# timerV2.net
KiCad netlist of a schematic drawn in EAGLE
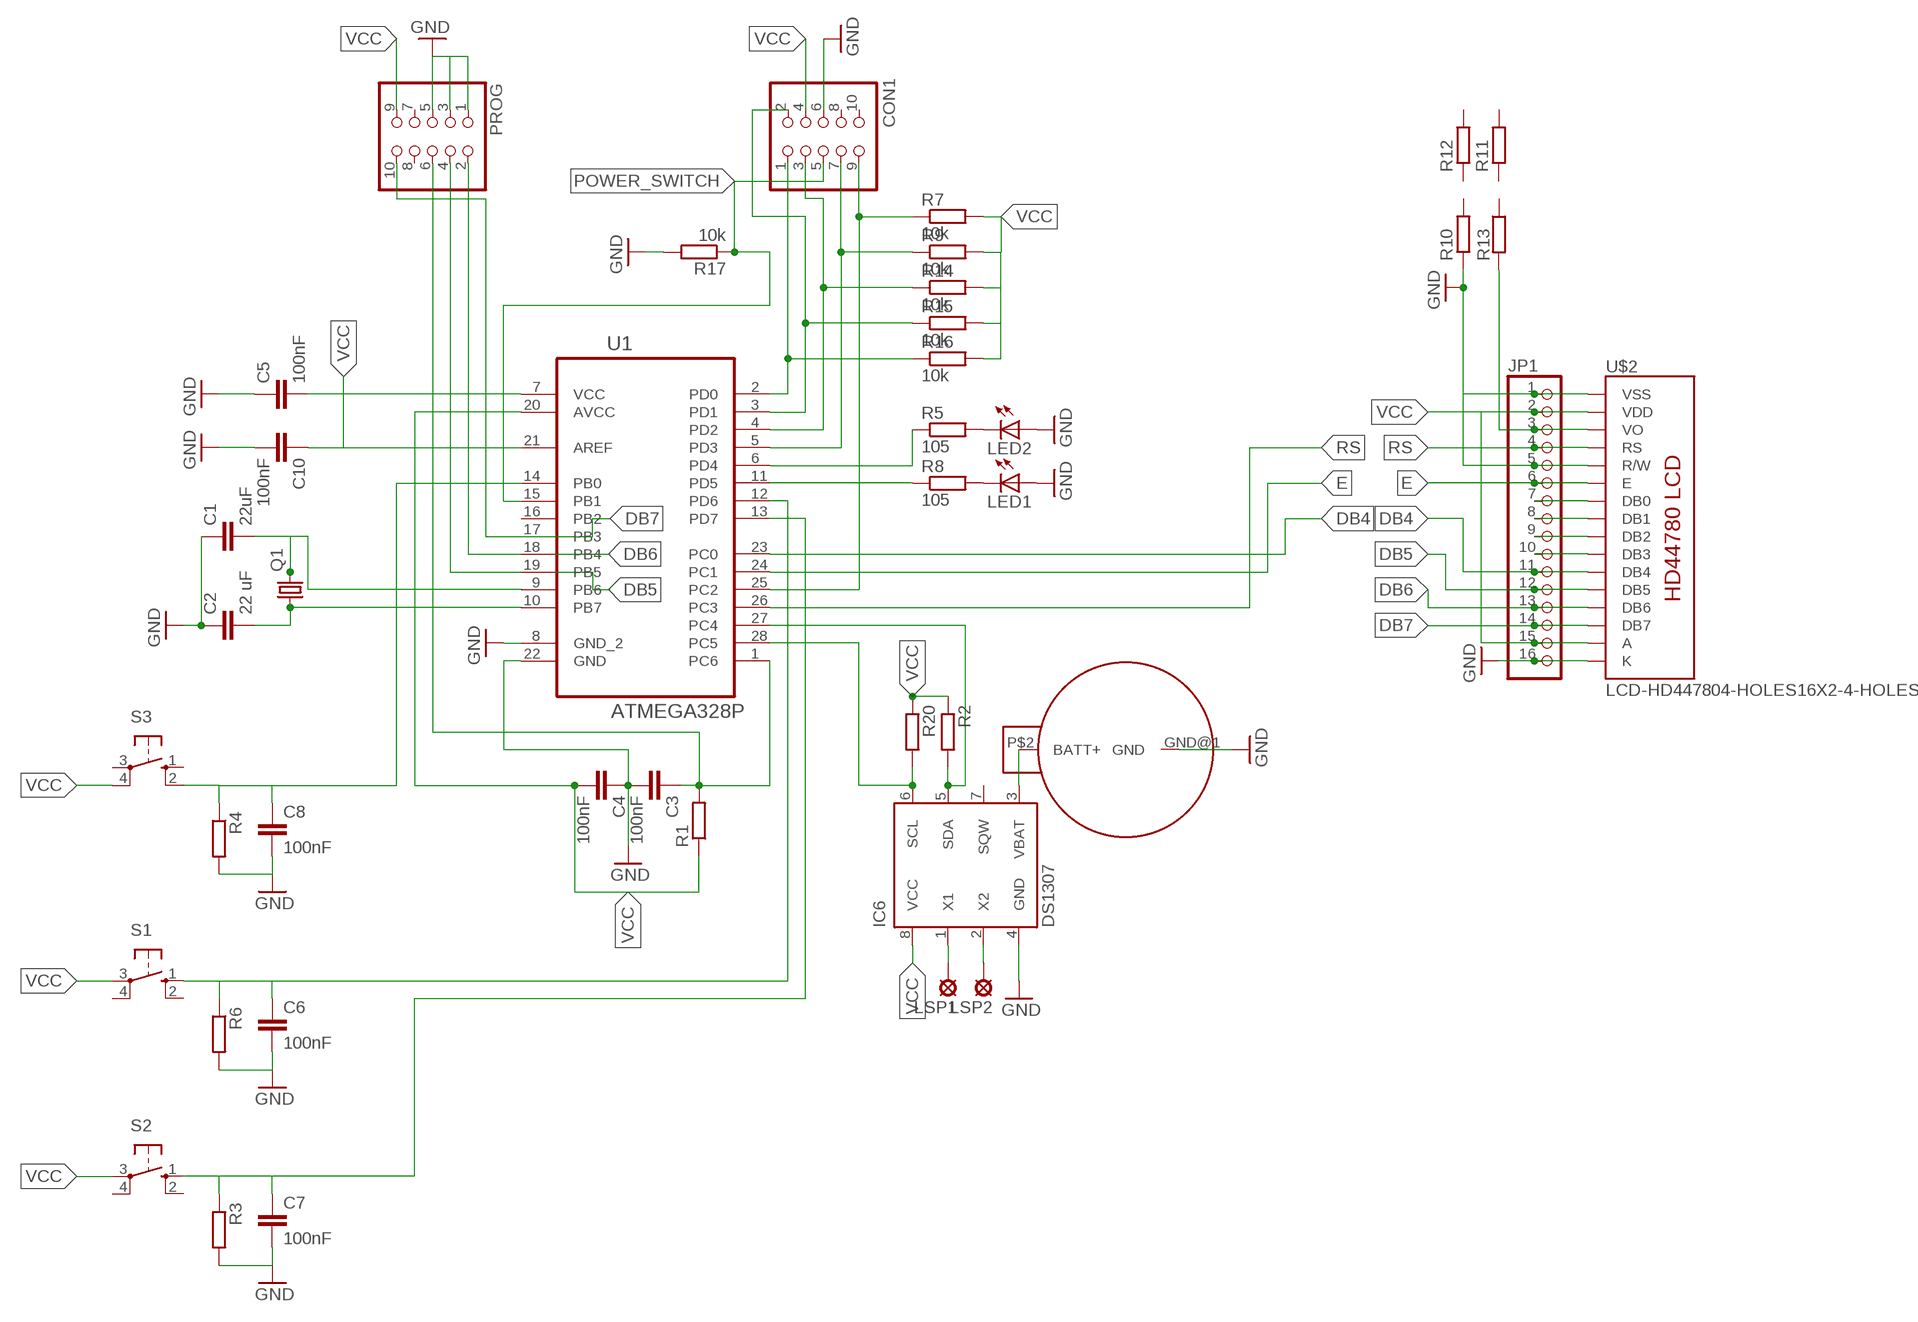
[diagram p0: schematic, sheet 1]

(export (version "E")
  (design (tool "Eeschema 10.0.6"))
  (components
    (comp (ref "C1")
      (value "22uF")
      (footprint "eagle-import:C025-025X050")
      (libsource (lib "eagle-import") (part "C-EU025-025X050"))
    )
    (comp (ref "C2")
      (value "22 uF")
      (footprint "eagle-import:C025-025X050")
      (libsource (lib "eagle-import") (part "C-EU025-025X050"))
    )
    (comp (ref "C3")
      (value "100nF")
      (footprint "eagle-import:C0603")
      (libsource (lib "eagle-import") (part "CC0603"))
    )
    (comp (ref "C4")
      (value "100nF")
      (footprint "eagle-import:C0603")
      (libsource (lib "eagle-import") (part "CC0603"))
    )
    (comp (ref "C5")
      (value "100nF")
      (footprint "eagle-import:C0603")
      (libsource (lib "eagle-import") (part "CC0603"))
    )
    (comp (ref "C6")
      (value "100nF")
      (footprint "eagle-import:C0603")
      (libsource (lib "eagle-import") (part "CC0603"))
    )
    (comp (ref "C7")
      (value "100nF")
      (footprint "eagle-import:C0603")
      (libsource (lib "eagle-import") (part "CC0603"))
    )
    (comp (ref "C8")
      (value "100nF")
      (footprint "eagle-import:C0603")
      (libsource (lib "eagle-import") (part "CC0603"))
    )
    (comp (ref "C10")
      (value "100nF")
      (footprint "eagle-import:C0603")
      (libsource (lib "eagle-import") (part "CC0603"))
    )
    (comp (ref "CON1")
      (value "PINHD-2X5")
      (footprint "eagle-import:2X05")
      (libsource (lib "eagle-import") (part "PINHD-2X5"))
    )
    (comp (ref "IC6")
      (value "DS1307")
      (footprint "eagle-import:DIL08")
      (libsource (lib "eagle-import") (part "DS1307"))
    )
    (comp (ref "JP1")
      (value "PINHD-1X16")
      (footprint "eagle-import:1X16")
      (libsource (lib "eagle-import") (part "PINHD-1X16"))
    )
    (comp (ref "LED1")
      (value "LED5MM")
      (footprint "eagle-import:LED5MM")
      (libsource (lib "eagle-import") (part "LED5MM"))
    )
    (comp (ref "LED2")
      (value "LED5MM")
      (footprint "eagle-import:LED5MM")
      (libsource (lib "eagle-import") (part "LED5MM"))
    )
    (comp (ref "LSP1")
      (value "LSP10")
      (footprint "eagle-import:LSP10")
      (libsource (lib "eagle-import") (part "LSP10"))
    )
    (comp (ref "LSP2")
      (value "LSP10")
      (footprint "eagle-import:LSP10")
      (libsource (lib "eagle-import") (part "LSP10"))
    )
    (comp (ref "PROG")
      (value "PINHD-2X5")
      (footprint "eagle-import:2X05")
      (libsource (lib "eagle-import") (part "PINHD-2X5"))
    )
    (comp (ref "Q1")
      (value "CRYSTALHC49U-V")
      (footprint "eagle-import:HC49U-V")
      (libsource (lib "eagle-import") (part "CRYSTALHC49U-V"))
    )
    (comp (ref "R1")
      (value "RR0603")
      (footprint "eagle-import:R0603")
      (libsource (lib "eagle-import") (part "RR0603"))
    )
    (comp (ref "R2")
      (value "RR0603")
      (footprint "eagle-import:R0603")
      (libsource (lib "eagle-import") (part "RR0603"))
    )
    (comp (ref "R3")
      (value "RR0603")
      (footprint "eagle-import:R0603")
      (libsource (lib "eagle-import") (part "RR0603"))
    )
    (comp (ref "R4")
      (value "RR0603")
      (footprint "eagle-import:R0603")
      (libsource (lib "eagle-import") (part "RR0603"))
    )
    (comp (ref "R5")
      (value "105")
      (footprint "eagle-import:R0603")
      (libsource (lib "eagle-import") (part "RR0603"))
    )
    (comp (ref "R6")
      (value "RR0603")
      (footprint "eagle-import:R0603")
      (libsource (lib "eagle-import") (part "RR0603"))
    )
    (comp (ref "R7")
      (value "10k")
      (footprint "eagle-import:R0603")
      (libsource (lib "eagle-import") (part "RR0603"))
    )
    (comp (ref "R8")
      (value "105")
      (footprint "eagle-import:R0603")
      (libsource (lib "eagle-import") (part "RR0603"))
    )
    (comp (ref "R9")
      (value "10k")
      (footprint "eagle-import:R0603")
      (libsource (lib "eagle-import") (part "RR0603"))
    )
    (comp (ref "R10")
      (value "RR0603")
      (footprint "eagle-import:R0603")
      (libsource (lib "eagle-import") (part "RR0603"))
    )
    (comp (ref "R11")
      (value "RR0603")
      (footprint "eagle-import:R0603")
      (libsource (lib "eagle-import") (part "RR0603"))
    )
    (comp (ref "R12")
      (value "RR0603")
      (footprint "eagle-import:R0603")
      (libsource (lib "eagle-import") (part "RR0603"))
    )
    (comp (ref "R13")
      (value "RR0603")
      (footprint "eagle-import:R0603")
      (libsource (lib "eagle-import") (part "RR0603"))
    )
    (comp (ref "R14")
      (value "10k")
      (footprint "eagle-import:R0603")
      (libsource (lib "eagle-import") (part "RR0603"))
    )
    (comp (ref "R15")
      (value "10k")
      (footprint "eagle-import:R0603")
      (libsource (lib "eagle-import") (part "RR0603"))
    )
    (comp (ref "R16")
      (value "10k")
      (footprint "eagle-import:R0603")
      (libsource (lib "eagle-import") (part "RR0603"))
    )
    (comp (ref "R17")
      (value "10k")
      (footprint "eagle-import:R0603")
      (libsource (lib "eagle-import") (part "RR0603"))
    )
    (comp (ref "R20")
      (value "RR0603")
      (footprint "eagle-import:R0603")
      (libsource (lib "eagle-import") (part "RR0603"))
    )
    (comp (ref "S1")
      (value "10-XX")
      (footprint "eagle-import:B3F-10XX")
      (fields (field (name "MPN") "B3F-1000"))
      (libsource (lib "eagle-import") (part "10-XX"))
    )
    (comp (ref "S2")
      (value "10-XX")
      (footprint "eagle-import:B3F-10XX")
      (fields (field (name "MPN") "B3F-1000"))
      (libsource (lib "eagle-import") (part "10-XX"))
    )
    (comp (ref "S3")
      (value "10-XX")
      (footprint "eagle-import:B3F-10XX")
      (fields (field (name "MPN") "B3F-1000"))
      (libsource (lib "eagle-import") (part "10-XX"))
    )
    (comp (ref "U$1")
      (value "CR2032")
      (footprint "eagle-import:CR2023")
      (libsource (lib "eagle-import") (part "CR2032"))
    )
    (comp (ref "U$2")
      (value "LCD-HD447804-HOLES16X2-4-HOLES")
      (footprint "eagle-import:LCD-16X2-4HOLES")
      (libsource (lib "eagle-import") (part "LCD-HD4478016X2-4-HOLES4-HOLES"))
    )
    (comp (ref "U1")
      (value "ATMEGA328P")
      (footprint "eagle-import:DIP254P762X457-28")
      (fields (field (name "MPN") "ATMEGA328P-PU"))
      (libsource (lib "eagle-import") (part "ATMEGA328P-PU"))
    )
  )
  (nets
    (net (code "1") (name "DB4") (class "Default")
      (node (ref "JP1") (pin "11") (pinfunction "11_11") (pintype "passive"))
      (node (ref "U$2") (pin "11") (pinfunction "DB4_11") (pintype "bidirectional"))
      (node (ref "U1") (pin "23") (pinfunction "PC0_23") (pintype "bidirectional"))
    )
    (net (code "2") (name "DB5") (class "Default")
      (node (ref "JP1") (pin "12") (pinfunction "12_12") (pintype "passive"))
      (node (ref "PROG") (pin "4") (pinfunction "4_4") (pintype "passive"))
      (node (ref "U$2") (pin "12") (pinfunction "DB5_12") (pintype "bidirectional"))
      (node (ref "U1") (pin "19") (pinfunction "PB5_19") (pintype "bidirectional"))
    )
    (net (code "3") (name "DB6") (class "Default")
      (node (ref "JP1") (pin "13") (pinfunction "13_13") (pintype "passive"))
      (node (ref "PROG") (pin "2") (pinfunction "2_2") (pintype "passive"))
      (node (ref "U$2") (pin "13") (pinfunction "DB6_13") (pintype "bidirectional"))
      (node (ref "U1") (pin "18") (pinfunction "PB4_18") (pintype "bidirectional"))
    )
    (net (code "4") (name "DB7") (class "Default")
      (node (ref "JP1") (pin "14") (pinfunction "14_14") (pintype "passive"))
      (node (ref "PROG") (pin "10") (pinfunction "10_10") (pintype "passive"))
      (node (ref "U$2") (pin "14") (pinfunction "DB7_14") (pintype "bidirectional"))
      (node (ref "U1") (pin "17") (pinfunction "PB3_17") (pintype "bidirectional"))
    )
    (net (code "5") (name "E") (class "Default")
      (node (ref "JP1") (pin "6") (pinfunction "6_6") (pintype "passive"))
      (node (ref "U$2") (pin "6") (pinfunction "E_6") (pintype "input"))
      (node (ref "U1") (pin "24") (pinfunction "PC1_24") (pintype "bidirectional"))
    )
    (net (code "6") (name "GND") (class "Default")
      (node (ref "C1") (pin "1") (pinfunction "1_1") (pintype "passive"))
      (node (ref "C10") (pin "2") (pinfunction "2_2") (pintype "passive"))
      (node (ref "C2") (pin "1") (pinfunction "1_1") (pintype "passive"))
      (node (ref "C3") (pin "2") (pinfunction "2_2") (pintype "passive"))
      (node (ref "C4") (pin "1") (pinfunction "1_1") (pintype "passive"))
      (node (ref "C5") (pin "1") (pinfunction "1_1") (pintype "passive"))
      (node (ref "C6") (pin "2") (pinfunction "2_2") (pintype "passive"))
      (node (ref "C7") (pin "2") (pinfunction "2_2") (pintype "passive"))
      (node (ref "C8") (pin "2") (pinfunction "2_2") (pintype "passive"))
      (node (ref "CON1") (pin "6") (pinfunction "6_6") (pintype "passive"))
      (node (ref "IC6") (pin "4") (pinfunction "GND_4") (pintype "power_in"))
      (node (ref "JP1") (pin "1") (pinfunction "1_1") (pintype "passive"))
      (node (ref "JP1") (pin "16") (pinfunction "16_16") (pintype "passive"))
      (node (ref "JP1") (pin "5") (pinfunction "5_5") (pintype "passive"))
      (node (ref "LED1") (pin "A") (pinfunction "A_A") (pintype "passive"))
      (node (ref "LED2") (pin "A") (pinfunction "A_A") (pintype "passive"))
      (node (ref "PROG") (pin "1") (pinfunction "1_1") (pintype "passive"))
      (node (ref "PROG") (pin "3") (pinfunction "3_3") (pintype "passive"))
      (node (ref "PROG") (pin "5") (pinfunction "5_5") (pintype "passive"))
      (node (ref "R10") (pin "1") (pinfunction "1_1") (pintype "passive"))
      (node (ref "R17") (pin "2") (pinfunction "2_2") (pintype "passive"))
      (node (ref "R3") (pin "2") (pinfunction "2_2") (pintype "passive"))
      (node (ref "R4") (pin "2") (pinfunction "2_2") (pintype "passive"))
      (node (ref "R6") (pin "2") (pinfunction "2_2") (pintype "passive"))
      (node (ref "U$1") (pin "GND@1") (pinfunction "GND_GND@1") (pintype "power_in"))
      (node (ref "U$2") (pin "1") (pinfunction "VSS_1") (pintype "power_in"))
      (node (ref "U$2") (pin "16") (pinfunction "K_16") (pintype "power_in"))
      (node (ref "U$2") (pin "5") (pinfunction "R/W_5") (pintype "input"))
      (node (ref "U1") (pin "22") (pinfunction "GND_22") (pintype "passive"))
      (node (ref "U1") (pin "8") (pinfunction "GND_2_8") (pintype "passive"))
    )
    (net (code "7") (name "Net-(IC6-SCL)") (class "Default")
      (node (ref "IC6") (pin "6") (pinfunction "SCL_6") (pintype "input"))
      (node (ref "R20") (pin "2") (pinfunction "2_2") (pintype "passive"))
      (node (ref "U1") (pin "28") (pinfunction "PC5_28") (pintype "bidirectional"))
    )
    (net (code "8") (name "Net-(IC6-SDA)") (class "Default")
      (node (ref "IC6") (pin "5") (pinfunction "SDA_5") (pintype "bidirectional"))
      (node (ref "R2") (pin "2") (pinfunction "2_2") (pintype "passive"))
      (node (ref "U1") (pin "27") (pinfunction "PC4_27") (pintype "bidirectional"))
    )
    (net (code "9") (name "Net-(IC6-VBAT)") (class "Default")
      (node (ref "IC6") (pin "3") (pinfunction "VBAT_3") (pintype "passive"))
      (node (ref "U$1") (pin "P$2") (pinfunction "BATT+_P$2") (pintype "output"))
    )
    (net (code "10") (name "Net-(IC6-X1)") (class "Default")
      (node (ref "IC6") (pin "1") (pinfunction "X1_1") (pintype "input"))
      (node (ref "LSP1") (pin "MP") (pinfunction "MP_MP") (pintype "passive"))
    )
    (net (code "11") (name "Net-(IC6-X2)") (class "Default")
      (node (ref "IC6") (pin "2") (pinfunction "X2_2") (pintype "output"))
      (node (ref "LSP2") (pin "MP") (pinfunction "MP_MP") (pintype "passive"))
    )
    (net (code "12") (name "Net-(LED1-C)") (class "Default")
      (node (ref "LED1") (pin "K") (pinfunction "C_K") (pintype "passive"))
      (node (ref "R8") (pin "2") (pinfunction "2_2") (pintype "passive"))
    )
    (net (code "13") (name "Net-(LED2-C)") (class "Default")
      (node (ref "LED2") (pin "K") (pinfunction "C_K") (pintype "passive"))
      (node (ref "R5") (pin "2") (pinfunction "2_2") (pintype "passive"))
    )
    (net (code "14") (name "Net-(S1-S)") (class "Default")
      (node (ref "C6") (pin "1") (pinfunction "1_1") (pintype "passive"))
      (node (ref "R6") (pin "1") (pinfunction "1_1") (pintype "passive"))
      (node (ref "S1") (pin "1") (pinfunction "S_1") (pintype "passive"))
      (node (ref "U1") (pin "12") (pinfunction "PD6_12") (pintype "bidirectional"))
    )
    (net (code "15") (name "Net-(S2-S)") (class "Default")
      (node (ref "C7") (pin "1") (pinfunction "1_1") (pintype "passive"))
      (node (ref "R3") (pin "1") (pinfunction "1_1") (pintype "passive"))
      (node (ref "S2") (pin "1") (pinfunction "S_1") (pintype "passive"))
      (node (ref "U1") (pin "13") (pinfunction "PD7_13") (pintype "bidirectional"))
    )
    (net (code "16") (name "Net-(S3-S1)") (class "Default")
      (node (ref "C8") (pin "1") (pinfunction "1_1") (pintype "passive"))
      (node (ref "R4") (pin "1") (pinfunction "1_1") (pintype "passive"))
      (node (ref "S3") (pin "2") (pinfunction "S1_2") (pintype "passive"))
      (node (ref "U1") (pin "14") (pinfunction "PB0_14") (pintype "bidirectional"))
    )
    (net (code "17") (name "Net-(U$2-DB0)") (class "Default")
      (node (ref "JP1") (pin "7") (pinfunction "7_7") (pintype "passive"))
      (node (ref "U$2") (pin "7") (pinfunction "DB0_7") (pintype "bidirectional"))
    )
    (net (code "18") (name "Net-(U$2-DB1)") (class "Default")
      (node (ref "JP1") (pin "8") (pinfunction "8_8") (pintype "passive"))
      (node (ref "U$2") (pin "8") (pinfunction "DB1_8") (pintype "bidirectional"))
    )
    (net (code "19") (name "Net-(U$2-DB2)") (class "Default")
      (node (ref "JP1") (pin "9") (pinfunction "9_9") (pintype "passive"))
      (node (ref "U$2") (pin "9") (pinfunction "DB2_9") (pintype "bidirectional"))
    )
    (net (code "20") (name "Net-(U$2-DB3)") (class "Default")
      (node (ref "JP1") (pin "10") (pinfunction "10_10") (pintype "passive"))
      (node (ref "U$2") (pin "10") (pinfunction "DB3_10") (pintype "bidirectional"))
    )
    (net (code "21") (name "Net-(U$2-VO)") (class "Default")
      (node (ref "JP1") (pin "3") (pinfunction "3_3") (pintype "passive"))
      (node (ref "R13") (pin "2") (pinfunction "2_2") (pintype "passive"))
      (node (ref "U$2") (pin "3") (pinfunction "VO_3") (pintype "bidirectional"))
    )
    (net (code "22") (name "Net-(U1-PB6)") (class "Default")
      (node (ref "C1") (pin "2") (pinfunction "2_2") (pintype "passive"))
      (node (ref "Q1") (pin "2") (pinfunction "2_2") (pintype "passive"))
      (node (ref "U1") (pin "9") (pinfunction "PB6_9") (pintype "bidirectional"))
    )
    (net (code "23") (name "Net-(U1-PB7)") (class "Default")
      (node (ref "C2") (pin "2") (pinfunction "2_2") (pintype "passive"))
      (node (ref "Q1") (pin "1") (pinfunction "1_1") (pintype "passive"))
      (node (ref "U1") (pin "10") (pinfunction "PB7_10") (pintype "bidirectional"))
    )
    (net (code "24") (name "Net-(U1-PC2)") (class "Default")
      (node (ref "CON1") (pin "9") (pinfunction "9_9") (pintype "passive"))
      (node (ref "R7") (pin "1") (pinfunction "1_1") (pintype "passive"))
      (node (ref "U1") (pin "25") (pinfunction "PC2_25") (pintype "bidirectional"))
    )
    (net (code "25") (name "Net-(U1-PC6)") (class "Default")
      (node (ref "C3") (pin "1") (pinfunction "1_1") (pintype "passive"))
      (node (ref "PROG") (pin "6") (pinfunction "6_6") (pintype "passive"))
      (node (ref "R1") (pin "2") (pinfunction "2_2") (pintype "passive"))
      (node (ref "U1") (pin "1") (pinfunction "PC6_1") (pintype "bidirectional"))
    )
    (net (code "26") (name "Net-(U1-PD0)") (class "Default")
      (node (ref "CON1") (pin "1") (pinfunction "1_1") (pintype "passive"))
      (node (ref "R16") (pin "1") (pinfunction "1_1") (pintype "passive"))
      (node (ref "U1") (pin "2") (pinfunction "PD0_2") (pintype "bidirectional"))
    )
    (net (code "27") (name "Net-(U1-PD1)") (class "Default")
      (node (ref "CON1") (pin "2") (pinfunction "2_2") (pintype "passive"))
      (node (ref "R15") (pin "1") (pinfunction "1_1") (pintype "passive"))
      (node (ref "U1") (pin "3") (pinfunction "PD1_3") (pintype "bidirectional"))
    )
    (net (code "28") (name "Net-(U1-PD2)") (class "Default")
      (node (ref "CON1") (pin "3") (pinfunction "3_3") (pintype "passive"))
      (node (ref "R14") (pin "1") (pinfunction "1_1") (pintype "passive"))
      (node (ref "U1") (pin "4") (pinfunction "PD2_4") (pintype "bidirectional"))
    )
    (net (code "29") (name "Net-(U1-PD3)") (class "Default")
      (node (ref "CON1") (pin "7") (pinfunction "7_7") (pintype "passive"))
      (node (ref "R9") (pin "1") (pinfunction "1_1") (pintype "passive"))
      (node (ref "U1") (pin "5") (pinfunction "PD3_5") (pintype "bidirectional"))
    )
    (net (code "30") (name "Net-(U1-PD4)") (class "Default")
      (node (ref "R5") (pin "1") (pinfunction "1_1") (pintype "passive"))
      (node (ref "U1") (pin "6") (pinfunction "PD4_6") (pintype "bidirectional"))
    )
    (net (code "31") (name "Net-(U1-PD5)") (class "Default")
      (node (ref "R8") (pin "1") (pinfunction "1_1") (pintype "passive"))
      (node (ref "U1") (pin "11") (pinfunction "PD5_11") (pintype "bidirectional"))
    )
    (net (code "32") (name "POWER_SWITCH") (class "Default")
      (node (ref "CON1") (pin "5") (pinfunction "5_5") (pintype "passive"))
      (node (ref "R17") (pin "1") (pinfunction "1_1") (pintype "passive"))
      (node (ref "U1") (pin "15") (pinfunction "PB1_15") (pintype "bidirectional"))
    )
    (net (code "33") (name "RS") (class "Default")
      (node (ref "JP1") (pin "4") (pinfunction "4_4") (pintype "passive"))
      (node (ref "U$2") (pin "4") (pinfunction "RS_4") (pintype "input"))
      (node (ref "U1") (pin "26") (pinfunction "PC3_26") (pintype "bidirectional"))
    )
    (net (code "34") (name "VCC") (class "Default")
      (node (ref "C10") (pin "1") (pinfunction "1_1") (pintype "passive"))
      (node (ref "C4") (pin "2") (pinfunction "2_2") (pintype "passive"))
      (node (ref "C5") (pin "2") (pinfunction "2_2") (pintype "passive"))
      (node (ref "CON1") (pin "4") (pinfunction "4_4") (pintype "passive"))
      (node (ref "IC6") (pin "8") (pinfunction "VCC_8") (pintype "power_in"))
      (node (ref "JP1") (pin "15") (pinfunction "15_15") (pintype "passive"))
      (node (ref "JP1") (pin "2") (pinfunction "2_2") (pintype "passive"))
      (node (ref "PROG") (pin "9") (pinfunction "9_9") (pintype "passive"))
      (node (ref "R1") (pin "1") (pinfunction "1_1") (pintype "passive"))
      (node (ref "R14") (pin "2") (pinfunction "2_2") (pintype "passive"))
      (node (ref "R15") (pin "2") (pinfunction "2_2") (pintype "passive"))
      (node (ref "R16") (pin "2") (pinfunction "2_2") (pintype "passive"))
      (node (ref "R2") (pin "1") (pinfunction "1_1") (pintype "passive"))
      (node (ref "R20") (pin "1") (pinfunction "1_1") (pintype "passive"))
      (node (ref "R7") (pin "2") (pinfunction "2_2") (pintype "passive"))
      (node (ref "R9") (pin "2") (pinfunction "2_2") (pintype "passive"))
      (node (ref "S1") (pin "3") (pinfunction "P_3") (pintype "passive"))
      (node (ref "S2") (pin "3") (pinfunction "P_3") (pintype "passive"))
      (node (ref "S3") (pin "4") (pinfunction "P1_4") (pintype "passive"))
      (node (ref "U$2") (pin "15") (pinfunction "A_15") (pintype "power_in"))
      (node (ref "U$2") (pin "2") (pinfunction "VDD_2") (pintype "power_in"))
      (node (ref "U1") (pin "20") (pinfunction "AVCC_20") (pintype "power_in"))
      (node (ref "U1") (pin "21") (pinfunction "AREF_21") (pintype "input"))
      (node (ref "U1") (pin "7") (pinfunction "VCC_7") (pintype "power_in"))
    )
    (net (code "35") (name "unconnected-(CON1-Pad8)") (class "Default")
      (node (ref "CON1") (pin "8") (pinfunction "8_8") (pintype "passive"))
    )
    (net (code "36") (name "unconnected-(CON1-Pad10)") (class "Default")
      (node (ref "CON1") (pin "10") (pinfunction "10_10") (pintype "passive"))
    )
    (net (code "37") (name "unconnected-(IC6-SQW-Pad7)") (class "Default")
      (node (ref "IC6") (pin "7") (pinfunction "SQW_7") (pintype "open_collector"))
    )
    (net (code "38") (name "unconnected-(PROG-Pad7)") (class "Default")
      (node (ref "PROG") (pin "7") (pinfunction "7_7") (pintype "passive"))
    )
    (net (code "39") (name "unconnected-(PROG-Pad8)") (class "Default")
      (node (ref "PROG") (pin "8") (pinfunction "8_8") (pintype "passive"))
    )
    (net (code "40") (name "unconnected-(R10-Pad2)") (class "Default")
      (node (ref "R10") (pin "2") (pinfunction "2_2") (pintype "passive"))
    )
    (net (code "41") (name "unconnected-(R11-Pad1)") (class "Default")
      (node (ref "R11") (pin "1") (pinfunction "1_1") (pintype "passive"))
    )
    (net (code "42") (name "unconnected-(R11-Pad2)") (class "Default")
      (node (ref "R11") (pin "2") (pinfunction "2_2") (pintype "passive"))
    )
    (net (code "43") (name "unconnected-(R12-Pad1)") (class "Default")
      (node (ref "R12") (pin "1") (pinfunction "1_1") (pintype "passive"))
    )
    (net (code "44") (name "unconnected-(R12-Pad2)") (class "Default")
      (node (ref "R12") (pin "2") (pinfunction "2_2") (pintype "passive"))
    )
    (net (code "45") (name "unconnected-(R13-Pad1)") (class "Default")
      (node (ref "R13") (pin "1") (pinfunction "1_1") (pintype "passive"))
    )
    (net (code "46") (name "unconnected-(S1-P1-Pad4)") (class "Default")
      (node (ref "S1") (pin "4") (pinfunction "P1_4") (pintype "passive"))
    )
    (net (code "47") (name "unconnected-(S1-S1-Pad2)") (class "Default")
      (node (ref "S1") (pin "2") (pinfunction "S1_2") (pintype "passive"))
    )
    (net (code "48") (name "unconnected-(S2-P1-Pad4)") (class "Default")
      (node (ref "S2") (pin "4") (pinfunction "P1_4") (pintype "passive"))
    )
    (net (code "49") (name "unconnected-(S2-S1-Pad2)") (class "Default")
      (node (ref "S2") (pin "2") (pinfunction "S1_2") (pintype "passive"))
    )
    (net (code "50") (name "unconnected-(S3-P-Pad3)") (class "Default")
      (node (ref "S3") (pin "3") (pinfunction "P_3") (pintype "passive"))
    )
    (net (code "51") (name "unconnected-(S3-S-Pad1)") (class "Default")
      (node (ref "S3") (pin "1") (pinfunction "S_1") (pintype "passive"))
    )
    (net (code "52") (name "unconnected-(U1-PB2-Pad16)") (class "Default")
      (node (ref "U1") (pin "16") (pinfunction "PB2_16") (pintype "bidirectional"))
    )
  )
)
